# MCU_Design_exp_neat.net
KiCad netlist of a schematic drawn in EAGLE
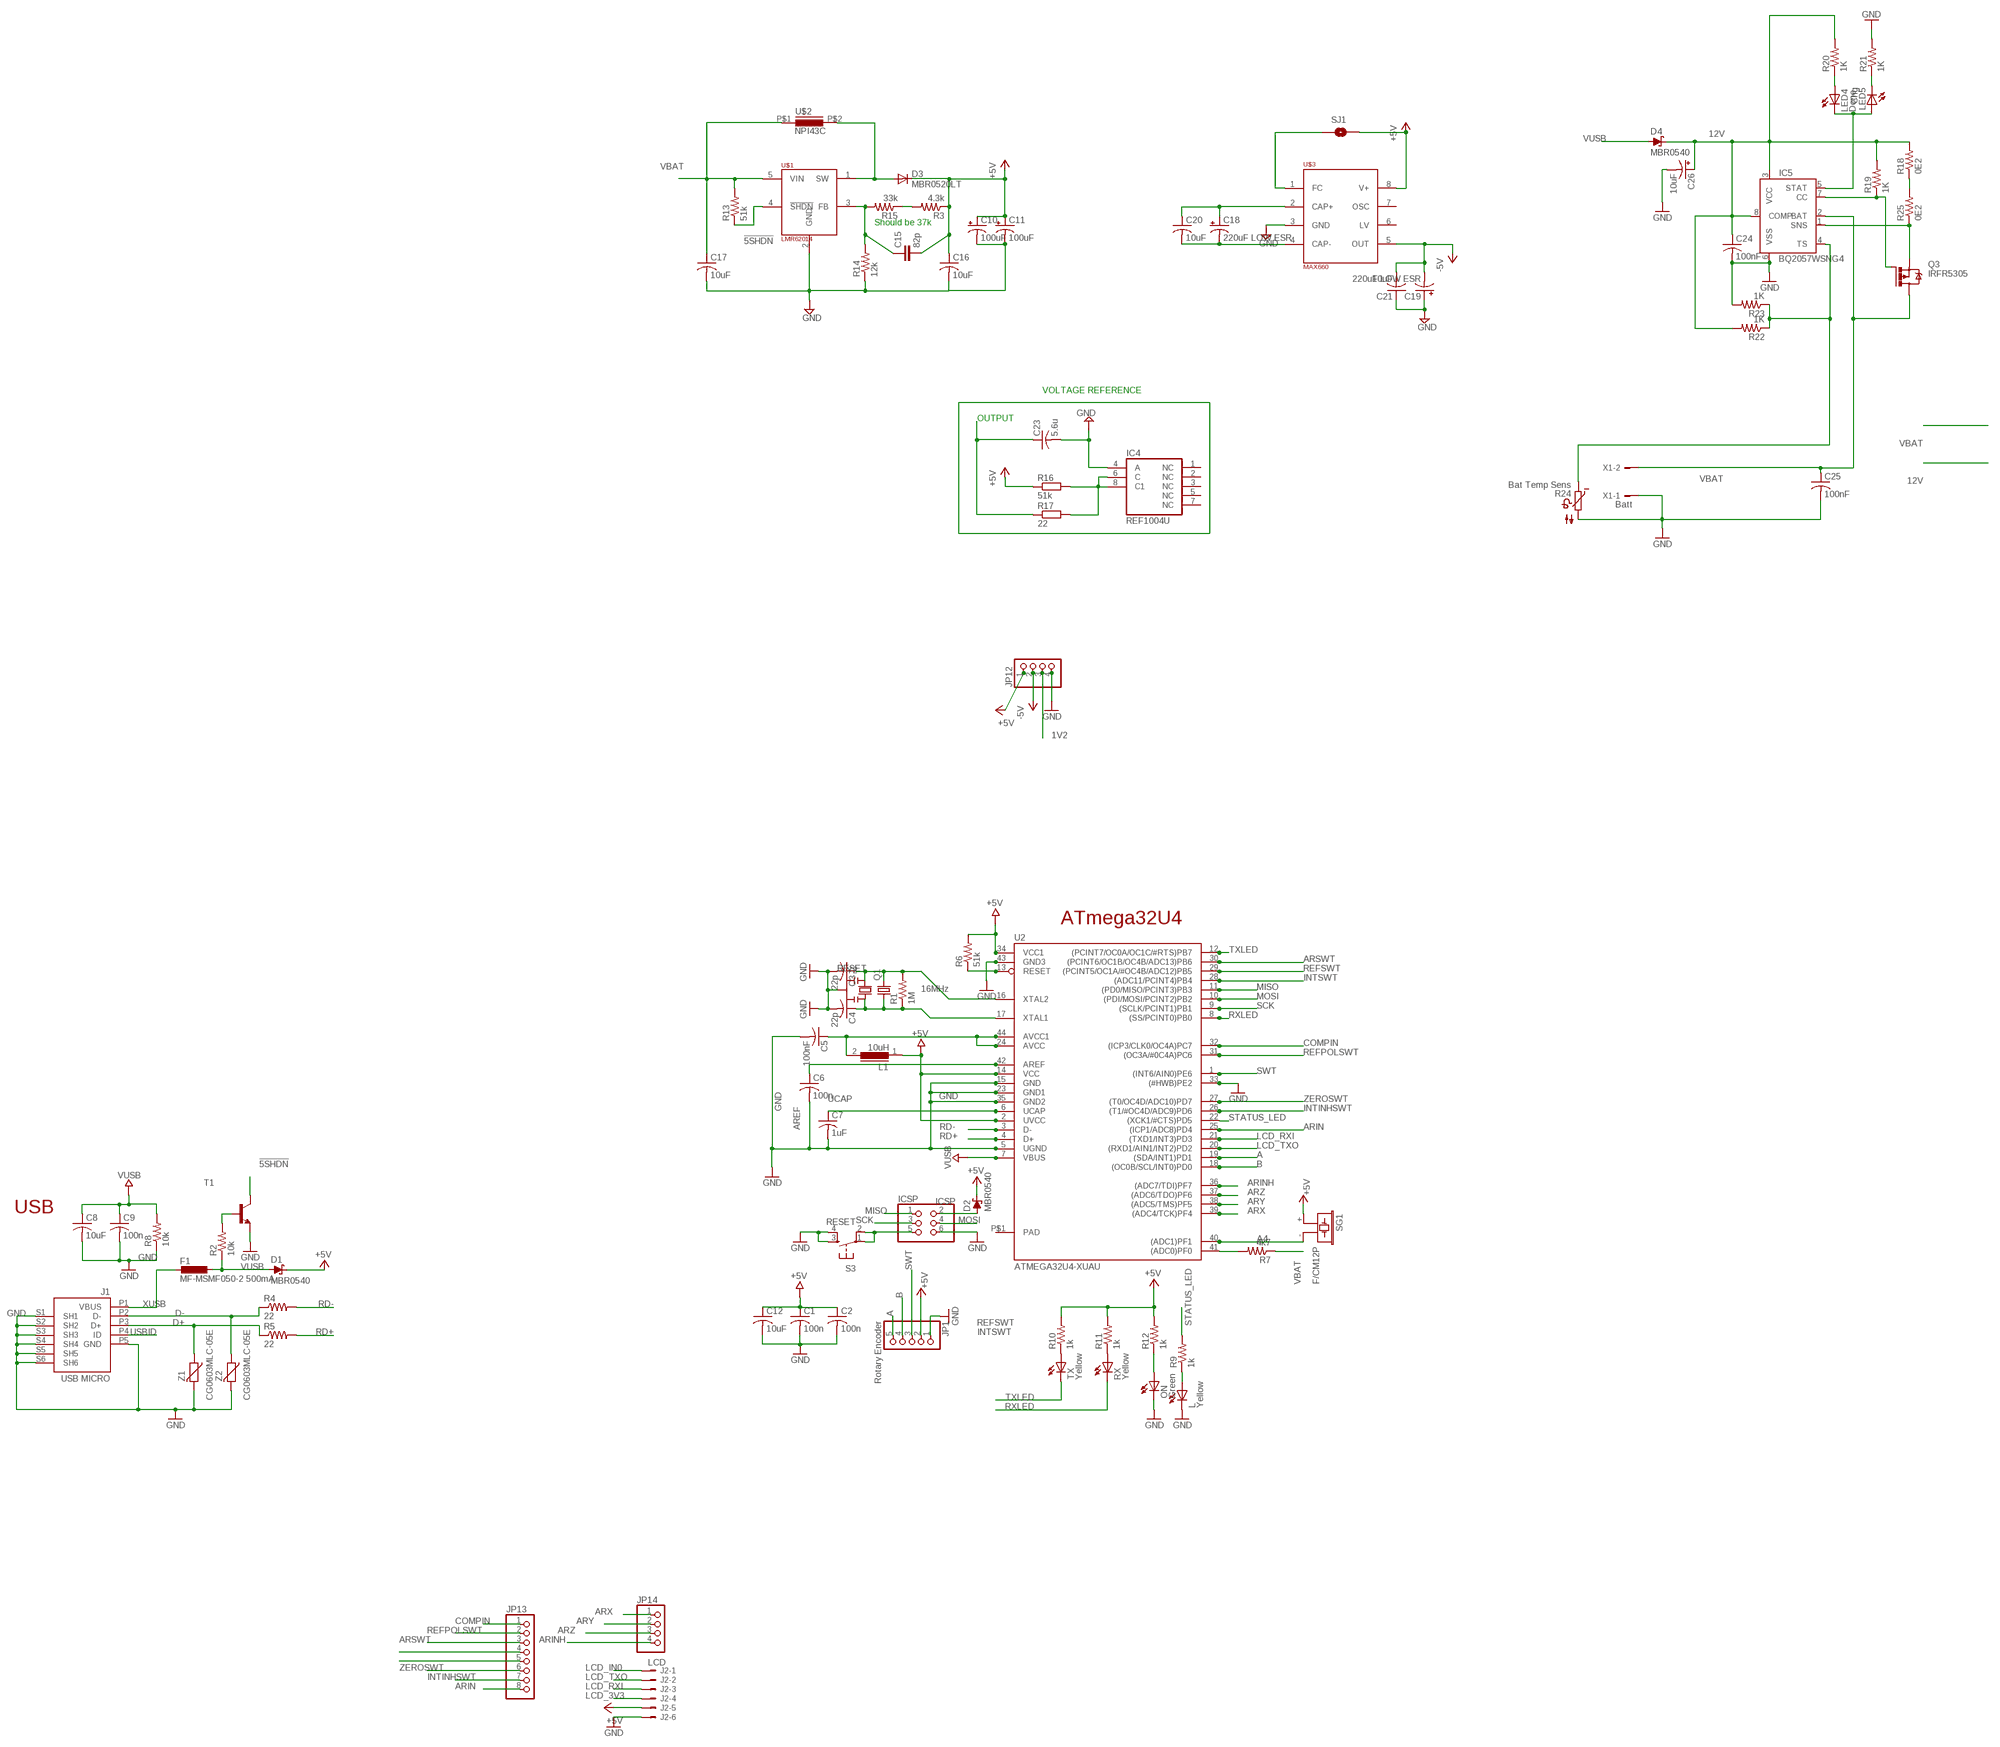
[diagram p0: schematic, sheet 1]

(export (version "E")
  (design (tool "Eeschema 10.0.6"))
  (components
    (comp (ref "C1")
      (value "100n")
      (footprint "eagle-import:C0805")
      (libsource (lib "eagle-import") (part "resistor_C-USC0805"))
    )
    (comp (ref "C2")
      (value "100n")
      (footprint "eagle-import:C0805")
      (libsource (lib "eagle-import") (part "resistor_C-USC0805"))
    )
    (comp (ref "C3")
      (value "22p")
      (footprint "eagle-import:C0805")
      (libsource (lib "eagle-import") (part "resistor_C-USC0805"))
    )
    (comp (ref "C4")
      (value "22p")
      (footprint "eagle-import:C0805")
      (libsource (lib "eagle-import") (part "resistor_C-USC0805"))
    )
    (comp (ref "C5")
      (value "100nF")
      (footprint "eagle-import:C0805")
      (libsource (lib "eagle-import") (part "resistor_C-USC0805"))
    )
    (comp (ref "C6")
      (value "100n")
      (footprint "eagle-import:C0805")
      (libsource (lib "eagle-import") (part "resistor_C-USC0805"))
    )
    (comp (ref "C7")
      (value "1uF")
      (footprint "eagle-import:C0805")
      (libsource (lib "eagle-import") (part "resistor_C-USC0805"))
    )
    (comp (ref "C8")
      (value "10uF")
      (footprint "eagle-import:C0805")
      (libsource (lib "eagle-import") (part "resistor_C-USC0805"))
    )
    (comp (ref "C9")
      (value "100n")
      (footprint "eagle-import:C0805")
      (libsource (lib "eagle-import") (part "resistor_C-USC0805"))
    )
    (comp (ref "C10")
      (value "100uF")
      (footprint "eagle-import:PANASONIC_D")
      (libsource (lib "eagle-import") (part "CPOL-USD"))
    )
    (comp (ref "C11")
      (value "100uF")
      (footprint "eagle-import:PANASONIC_D")
      (libsource (lib "eagle-import") (part "CPOL-USD"))
    )
    (comp (ref "C12")
      (value "10uF")
      (footprint "eagle-import:C0805")
      (libsource (lib "eagle-import") (part "resistor_C-USC0805"))
    )
    (comp (ref "C15")
      (value "82p")
      (footprint "eagle-import:C0805")
      (libsource (lib "eagle-import") (part "C-EUC0805"))
    )
    (comp (ref "C16")
      (value "10uF")
      (footprint "eagle-import:C0805")
      (libsource (lib "eagle-import") (part "resistor_C-USC0805"))
    )
    (comp (ref "C17")
      (value "10uF")
      (footprint "eagle-import:C0805")
      (libsource (lib "eagle-import") (part "resistor_C-USC0805"))
    )
    (comp (ref "C18")
      (value "220uF LOW ESR")
      (footprint "eagle-import:PANASONIC_D")
      (libsource (lib "eagle-import") (part "CPOL-USD"))
    )
    (comp (ref "C19")
      (value "220uF LOW ESR")
      (footprint "eagle-import:PANASONIC_D")
      (libsource (lib "eagle-import") (part "CPOL-USD"))
    )
    (comp (ref "C20")
      (value "10uF")
      (footprint "eagle-import:C0805")
      (libsource (lib "eagle-import") (part "resistor_C-USC0805"))
    )
    (comp (ref "C21")
      (value "10uF")
      (footprint "eagle-import:C0805")
      (libsource (lib "eagle-import") (part "resistor_C-USC0805"))
    )
    (comp (ref "C23")
      (value "5.6u")
      (footprint "eagle-import:C0805K")
      (libsource (lib "eagle-import") (part "C-USC0805K"))
    )
    (comp (ref "C24")
      (value "100nF")
      (footprint "eagle-import:C0805K")
      (libsource (lib "eagle-import") (part "resistor_C-USC0805K"))
    )
    (comp (ref "C25")
      (value "100nF")
      (footprint "eagle-import:C0805K")
      (libsource (lib "eagle-import") (part "resistor_C-USC0805K"))
    )
    (comp (ref "C26")
      (value "10uF")
      (footprint "eagle-import:153CLV-0405")
      (libsource (lib "eagle-import") (part "CPOL-US153CLV-0405"))
    )
    (comp (ref "D1")
      (value "MBR0540")
      (footprint "eagle-import:SOD123@2")
      (libsource (lib "eagle-import") (part "MBR0540"))
    )
    (comp (ref "D2")
      (value "MBR0540")
      (footprint "eagle-import:SOD123@2")
      (libsource (lib "eagle-import") (part "MBR0540"))
    )
    (comp (ref "D3")
      (value "MBR0520LT")
      (footprint "eagle-import:SOD123")
      (libsource (lib "eagle-import") (part "MBR0520LT"))
    )
    (comp (ref "D4")
      (value "MBR0540")
      (footprint "eagle-import:SOD123@2")
      (libsource (lib "eagle-import") (part "MBR0540"))
    )
    (comp (ref "F1")
      (value "MF-MSMF050-2 500mA")
      (footprint "eagle-import:L1812")
      (libsource (lib "eagle-import") (part "L-EUL1812"))
    )
    (comp (ref "IC4")
      (value "REF1004U")
      (footprint "eagle-import:SO08")
      (fields (field (name "MF") "TEXAS INSTRUMENTS") (field (name "MPN") "REF1004C-1.2"))
      (libsource (lib "eagle-import") (part "REF1004U"))
    )
    (comp (ref "IC5")
      (value "BQ2057WSNG4")
      (footprint "eagle-import:D_R-PDSO-G8")
      (libsource (lib "eagle-import") (part "BQ2057WSNG4"))
    )
    (comp (ref "ICSP")
      (value "ICSP")
      (footprint "eagle-import:2X03")
      (libsource (lib "eagle-import") (part "PINHD-2X3"))
    )
    (comp (ref "J1")
      (value "USB MICRO")
      (footprint "eagle-import:CON2_USB_MICRO_B_AT")
      (libsource (lib "eagle-import") (part "MYCON2_USB-MINI-B"))
    )
    (comp (ref "J2")
      (value "LCD")
      (footprint "eagle-import:7395-06")
      (libsource (lib "eagle-import") (part "22-?-0605-7068"))
    )
    (comp (ref "JP1")
      (value "Rotary Encoder")
      (footprint "eagle-import:1X05")
      (libsource (lib "eagle-import") (part "PINHD-1X5"))
    )
    (comp (ref "JP12")
      (value "PINHD-1X4")
      (footprint "eagle-import:1X04")
      (libsource (lib "eagle-import") (part "PINHD-1X4"))
    )
    (comp (ref "JP13")
      (value "PINHD-1X8")
      (footprint "eagle-import:1X08")
      (libsource (lib "eagle-import") (part "PINHD-1X8"))
    )
    (comp (ref "JP14")
      (value "PINHD-1X4")
      (footprint "eagle-import:1X04")
      (libsource (lib "eagle-import") (part "PINHD-1X4"))
    )
    (comp (ref "L")
      (value "Yellow")
      (footprint "eagle-import:CHIPLED_0805")
      (libsource (lib "eagle-import") (part "LEDCHIPLED_0805"))
    )
    (comp (ref "L1")
      (value "10uH")
      (footprint "eagle-import:MMICC7")
      (libsource (lib "eagle-import") (part "MMICC7"))
    )
    (comp (ref "LED4")
      (value "Done")
      (footprint "eagle-import:CHIPLED_0805")
      (libsource (lib "eagle-import") (part "LEDCHIPLED_0805"))
    )
    (comp (ref "LED5")
      (value "Chg")
      (footprint "eagle-import:CHIPLED_0805")
      (libsource (lib "eagle-import") (part "LEDCHIPLED_0805"))
    )
    (comp (ref "ON")
      (value "Green")
      (footprint "eagle-import:CHIPLED_0805")
      (libsource (lib "eagle-import") (part "LEDCHIPLED_0805"))
    )
    (comp (ref "Q1")
      (value "CRYSTALHC49UP")
      (footprint "eagle-import:HC49UP")
      (libsource (lib "eagle-import") (part "CRYSTALHC49UP"))
    )
    (comp (ref "Q3")
      (value "IRFR5305")
      (footprint "eagle-import:D-PAK_TO252AA")
      (libsource (lib "eagle-import") (part "IRF?5305R"))
    )
    (comp (ref "R1")
      (value "1M")
      (footprint "eagle-import:R0805")
      (libsource (lib "eagle-import") (part "R-US_R0805"))
    )
    (comp (ref "R2")
      (value "10k")
      (footprint "eagle-import:R0805")
      (libsource (lib "eagle-import") (part "R-US_R0805"))
    )
    (comp (ref "R3")
      (value "4.3k")
      (footprint "eagle-import:R0805")
      (libsource (lib "eagle-import") (part "R-US_R0805"))
    )
    (comp (ref "R4")
      (value "22")
      (footprint "eagle-import:R0805")
      (libsource (lib "eagle-import") (part "R-US_R0805"))
    )
    (comp (ref "R5")
      (value "22")
      (footprint "eagle-import:R0805")
      (libsource (lib "eagle-import") (part "R-US_R0805"))
    )
    (comp (ref "R6")
      (value "51k")
      (footprint "eagle-import:R0805")
      (libsource (lib "eagle-import") (part "R-US_R0805"))
    )
    (comp (ref "R7")
      (value "4k7")
      (footprint "eagle-import:R0805")
      (libsource (lib "eagle-import") (part "R-US_R0805"))
    )
    (comp (ref "R8")
      (value "10k")
      (footprint "eagle-import:R0805")
      (libsource (lib "eagle-import") (part "R-US_R0805"))
    )
    (comp (ref "R9")
      (value "1k")
      (footprint "eagle-import:R0805")
      (libsource (lib "eagle-import") (part "R-US_R0805"))
    )
    (comp (ref "R10")
      (value "1k")
      (footprint "eagle-import:R0805")
      (libsource (lib "eagle-import") (part "R-US_R0805"))
    )
    (comp (ref "R11")
      (value "1k")
      (footprint "eagle-import:R0805")
      (libsource (lib "eagle-import") (part "R-US_R0805"))
    )
    (comp (ref "R12")
      (value "1k")
      (footprint "eagle-import:R0805")
      (libsource (lib "eagle-import") (part "R-US_R0805"))
    )
    (comp (ref "R13")
      (value "51k")
      (footprint "eagle-import:R0805")
      (libsource (lib "eagle-import") (part "R-US_R0805"))
    )
    (comp (ref "R14")
      (value "12k")
      (footprint "eagle-import:R0805")
      (libsource (lib "eagle-import") (part "R-US_R0805"))
    )
    (comp (ref "R15")
      (value "33k")
      (footprint "eagle-import:R0805")
      (libsource (lib "eagle-import") (part "R-US_R0805"))
    )
    (comp (ref "R16")
      (value "51k")
      (footprint "eagle-import:M0805")
      (libsource (lib "eagle-import") (part "R-EU_M0805"))
    )
    (comp (ref "R17")
      (value "22")
      (footprint "eagle-import:M0805")
      (libsource (lib "eagle-import") (part "R-EU_M0805"))
    )
    (comp (ref "R18")
      (value "0E2")
      (footprint "eagle-import:M1206")
      (libsource (lib "eagle-import") (part "R-US_M1206"))
    )
    (comp (ref "R19")
      (value "1K")
      (footprint "eagle-import:R0805")
      (libsource (lib "eagle-import") (part "R-US_R0805"))
    )
    (comp (ref "R20")
      (value "1K")
      (footprint "eagle-import:R0805")
      (libsource (lib "eagle-import") (part "R-US_R0805"))
    )
    (comp (ref "R21")
      (value "1K")
      (footprint "eagle-import:R0805")
      (libsource (lib "eagle-import") (part "R-US_R0805"))
    )
    (comp (ref "R22")
      (value "1K")
      (footprint "eagle-import:R0805")
      (libsource (lib "eagle-import") (part "R-US_R0805"))
    )
    (comp (ref "R23")
      (value "1K")
      (footprint "eagle-import:R0805")
      (libsource (lib "eagle-import") (part "R-US_R0805"))
    )
    (comp (ref "R24")
      (value "Bat Temp Sens")
      (footprint "eagle-import:P640")
      (libsource (lib "eagle-import") (part "NTC640"))
    )
    (comp (ref "R25")
      (value "0E2")
      (footprint "eagle-import:M1206")
      (libsource (lib "eagle-import") (part "R-US_M1206"))
    )
    (comp (ref "RX")
      (value "Yellow")
      (footprint "eagle-import:CHIPLED_0805")
      (libsource (lib "eagle-import") (part "LEDCHIPLED_0805"))
    )
    (comp (ref "S3")
      (value "RESET")
      (footprint "eagle-import:TACTILE_SWITCH_SMD")
      (libsource (lib "eagle-import") (part "TAC_SWITCHSMD"))
    )
    (comp (ref "SG1")
      (value "F/CM12P")
      (footprint "eagle-import:F_CM12P")
      (libsource (lib "eagle-import") (part "F/CM12P"))
    )
    (comp (ref "SJ1")
      (value "SOLDERJUMPERTRACE")
      (footprint "eagle-import:SJ_2S-TRACE")
      (libsource (lib "eagle-import") (part "SOLDERJUMPERTRACE"))
    )
    (comp (ref "T1")
      (value "MMBT2222ALT1-NPN-SOT23-BEC")
      (footprint "eagle-import:SOT23-BEC")
      (libsource (lib "eagle-import") (part "-NPN-SOT23-BECMMBT2222ALT1"))
    )
    (comp (ref "TX")
      (value "Yellow")
      (footprint "eagle-import:CHIPLED_0805")
      (libsource (lib "eagle-import") (part "LEDCHIPLED_0805"))
    )
    (comp (ref "U$1")
      (value "LMR62014")
      (footprint "eagle-import:SOT23-5")
      (libsource (lib "eagle-import") (part "LMR62014"))
    )
    (comp (ref "U$2")
      (value "NPI43C")
      (footprint "eagle-import:NPI43C")
      (libsource (lib "eagle-import") (part "NPI43C"))
    )
    (comp (ref "U$3")
      (value "MAX660")
      (footprint "eagle-import:SO08")
      (libsource (lib "eagle-import") (part "MAX660"))
    )
    (comp (ref "U2")
      (value "ATMEGA32U4-XUAU")
      (footprint "eagle-import:TQFP44-PAD")
      (libsource (lib "eagle-import") (part "ATMEGA32U4-XUAU"))
    )
    (comp (ref "X1")
      (value "Batt")
      (footprint "eagle-import:22-23-2021")
      (fields (field (name "MF") "MOLEX") (field (name "MPN") "22-23-2021"))
      (libsource (lib "eagle-import") (part "22-23-2021"))
    )
    (comp (ref "Y2")
      (value "16MHz")
      (footprint "eagle-import:RESONATOR")
      (libsource (lib "eagle-import") (part "RESONATORMU"))
    )
    (comp (ref "Z1")
      (value "CG0603MLC-05E")
      (footprint "eagle-import:CT_CN0603")
      (libsource (lib "eagle-import") (part "VARISTORCN0603"))
    )
    (comp (ref "Z2")
      (value "CG0603MLC-05E")
      (footprint "eagle-import:CT_CN0603")
      (libsource (lib "eagle-import") (part "VARISTORCN0603"))
    )
  )
  (nets
    (net (code "1") (name "+5V") (class "Default")
      (node (ref "C1") (pin "1") (pinfunction "1_1") (pintype "passive"))
      (node (ref "C10") (pin "+") (pinfunction "+_+") (pintype "passive"))
      (node (ref "C11") (pin "+") (pinfunction "+_+") (pintype "passive"))
      (node (ref "C12") (pin "1") (pinfunction "1_1") (pintype "passive"))
      (node (ref "C15") (pin "2") (pinfunction "2_2") (pintype "passive"))
      (node (ref "C16") (pin "1") (pinfunction "1_1") (pintype "passive"))
      (node (ref "C2") (pin "1") (pinfunction "1_1") (pintype "passive"))
      (node (ref "D1") (pin "C") (pinfunction "C_C") (pintype "passive"))
      (node (ref "D2") (pin "C") (pinfunction "C_C") (pintype "passive"))
      (node (ref "D3") (pin "C") (pinfunction "C_C") (pintype "passive"))
      (node (ref "J2") (pin "5") (pinfunction "S_5") (pintype "passive"))
      (node (ref "JP1") (pin "2") (pinfunction "2_2") (pintype "passive"))
      (node (ref "JP12") (pin "1") (pinfunction "1_1") (pintype "passive"))
      (node (ref "L1") (pin "1") (pinfunction "1_1") (pintype "passive"))
      (node (ref "R10") (pin "2") (pinfunction "2_2") (pintype "passive"))
      (node (ref "R11") (pin "2") (pinfunction "2_2") (pintype "passive"))
      (node (ref "R12") (pin "2") (pinfunction "2_2") (pintype "passive"))
      (node (ref "R16") (pin "1") (pinfunction "1_1") (pintype "passive"))
      (node (ref "R3") (pin "1") (pinfunction "1_1") (pintype "passive"))
      (node (ref "R6") (pin "2") (pinfunction "2_2") (pintype "passive"))
      (node (ref "SG1") (pin "+") (pinfunction "1_+") (pintype "passive"))
      (node (ref "SJ1") (pin "2") (pinfunction "2_2") (pintype "passive"))
      (node (ref "U$3") (pin "8") (pinfunction "V+_8") (pintype "bidirectional"))
      (node (ref "U2") (pin "14") (pinfunction "VCC_14") (pintype "power_in"))
      (node (ref "U2") (pin "2") (pinfunction "UVCC_2") (pintype "power_in"))
      (node (ref "U2") (pin "34") (pinfunction "VCC1_34") (pintype "power_in"))
    )
    (net (code "2") (name "-5V") (class "Default")
      (node (ref "C19") (pin "-") (pinfunction "-_-") (pintype "passive"))
      (node (ref "C21") (pin "2") (pinfunction "2_2") (pintype "passive"))
      (node (ref "JP12") (pin "2") (pinfunction "2_2") (pintype "passive"))
      (node (ref "U$3") (pin "5") (pinfunction "OUT_5") (pintype "bidirectional"))
    )
    (net (code "3") (name "/1V2") (class "Default")
      (node (ref "C23") (pin "1") (pinfunction "1_1") (pintype "passive"))
      (node (ref "JP12") (pin "3") (pinfunction "3_3") (pintype "passive"))
      (node (ref "R17") (pin "1") (pinfunction "1_1") (pintype "passive"))
    )
    (net (code "4") (name "/12V") (class "Default")
      (node (ref "C24") (pin "1") (pinfunction "1_1") (pintype "passive"))
      (node (ref "C26") (pin "+") (pinfunction "+_+") (pintype "passive"))
      (node (ref "D4") (pin "C") (pinfunction "C_C") (pintype "passive"))
      (node (ref "IC5") (pin "3") (pinfunction "VCC_3") (pintype "input"))
      (node (ref "IC5") (pin "8") (pinfunction "COMP_8") (pintype "input"))
      (node (ref "R18") (pin "2") (pinfunction "2_2") (pintype "passive"))
      (node (ref "R19") (pin "2") (pinfunction "2_2") (pintype "passive"))
      (node (ref "R20") (pin "2") (pinfunction "2_2") (pintype "passive"))
      (node (ref "R22") (pin "2") (pinfunction "2_2") (pintype "passive"))
    )
    (net (code "5") (name "/A") (class "Default")
      (node (ref "JP1") (pin "5") (pinfunction "5_5") (pintype "passive"))
      (node (ref "U2") (pin "19") (pinfunction "(SDA/INT1)PD1_19") (pintype "bidirectional"))
    )
    (net (code "6") (name "/A4") (class "Default")
      (node (ref "SG1") (pin "-") (pinfunction "2_-") (pintype "passive"))
      (node (ref "U2") (pin "40") (pinfunction "(ADC1)PF1_40") (pintype "bidirectional"))
    )
    (net (code "7") (name "/AREF") (class "Default")
      (node (ref "C6") (pin "1") (pinfunction "1_1") (pintype "passive"))
      (node (ref "U2") (pin "42") (pinfunction "AREF_42") (pintype "power_in"))
    )
    (net (code "8") (name "/ARIN") (class "Default")
      (node (ref "JP13") (pin "8") (pinfunction "8_8") (pintype "passive"))
      (node (ref "U2") (pin "25") (pinfunction "(ICP1/ADC8)PD4_25") (pintype "bidirectional"))
    )
    (net (code "9") (name "/ARINH") (class "Default")
      (node (ref "JP14") (pin "4") (pinfunction "4_4") (pintype "passive"))
      (node (ref "U2") (pin "36") (pinfunction "(ADC7/TDI)PF7_36") (pintype "bidirectional"))
    )
    (net (code "10") (name "/ARSWT") (class "Default")
      (node (ref "JP13") (pin "3") (pinfunction "3_3") (pintype "passive"))
      (node (ref "U2") (pin "30") (pinfunction "(PCINT6/OC1B/OC4B/ADC13)PB6_30") (pintype "bidirectional"))
    )
    (net (code "11") (name "/ARX") (class "Default")
      (node (ref "JP14") (pin "1") (pinfunction "1_1") (pintype "passive"))
      (node (ref "U2") (pin "39") (pinfunction "(ADC4/TCK)PF4_39") (pintype "bidirectional"))
    )
    (net (code "12") (name "/ARY") (class "Default")
      (node (ref "JP14") (pin "2") (pinfunction "2_2") (pintype "passive"))
      (node (ref "U2") (pin "38") (pinfunction "(ADC5/TMS)PF5_38") (pintype "bidirectional"))
    )
    (net (code "13") (name "/ARZ") (class "Default")
      (node (ref "JP14") (pin "3") (pinfunction "3_3") (pintype "passive"))
      (node (ref "U2") (pin "37") (pinfunction "(ADC6/TDO)PF6_37") (pintype "bidirectional"))
    )
    (net (code "14") (name "/B") (class "Default")
      (node (ref "JP1") (pin "4") (pinfunction "4_4") (pintype "passive"))
      (node (ref "U2") (pin "18") (pinfunction "(OC0B/SCL/INT0)PD0_18") (pintype "bidirectional"))
    )
    (net (code "15") (name "/COMPIN") (class "Default")
      (node (ref "JP13") (pin "1") (pinfunction "1_1") (pintype "passive"))
      (node (ref "U2") (pin "32") (pinfunction "(ICP3/CLK0/OC4A)PC7_32") (pintype "bidirectional"))
    )
    (net (code "16") (name "/D+") (class "Default")
      (node (ref "J1") (pin "P3") (pinfunction "D+_P3") (pintype "bidirectional"))
      (node (ref "R5") (pin "1") (pinfunction "1_1") (pintype "passive"))
      (node (ref "Z1") (pin "1") (pinfunction "1_1") (pintype "passive"))
    )
    (net (code "17") (name "/D-") (class "Default")
      (node (ref "J1") (pin "P2") (pinfunction "D-_P2") (pintype "bidirectional"))
      (node (ref "R4") (pin "1") (pinfunction "1_1") (pintype "passive"))
      (node (ref "Z2") (pin "1") (pinfunction "1_1") (pintype "passive"))
    )
    (net (code "18") (name "/INTINHSWT") (class "Default")
      (node (ref "JP13") (pin "7") (pinfunction "7_7") (pintype "passive"))
      (node (ref "U2") (pin "26") (pinfunction "(T1/#OC4D/ADC9)PD6_26") (pintype "bidirectional"))
    )
    (net (code "19") (name "/INTSWT") (class "Default")
      (node (ref "JP13") (pin "5") (pinfunction "5_5") (pintype "passive"))
      (node (ref "U2") (pin "28") (pinfunction "(ADC11/PCINT4)PB4_28") (pintype "bidirectional"))
    )
    (net (code "20") (name "/LCD_3V3") (class "Default")
      (node (ref "J2") (pin "4") (pinfunction "S_4") (pintype "passive"))
    )
    (net (code "21") (name "/LCD_IN0") (class "Default")
      (node (ref "J2") (pin "1") (pinfunction "S_1") (pintype "passive"))
    )
    (net (code "22") (name "/LCD_RXI") (class "Default")
      (node (ref "J2") (pin "3") (pinfunction "S_3") (pintype "passive"))
      (node (ref "U2") (pin "21") (pinfunction "(TXD1/INT3)PD3_21") (pintype "bidirectional"))
    )
    (net (code "23") (name "/LCD_TXO") (class "Default")
      (node (ref "J2") (pin "2") (pinfunction "S_2") (pintype "passive"))
      (node (ref "U2") (pin "20") (pinfunction "(RXD1/AIN1/INT2)PD2_20") (pintype "bidirectional"))
    )
    (net (code "24") (name "/MISO") (class "Default")
      (node (ref "ICSP") (pin "1") (pinfunction "1_1") (pintype "passive"))
      (node (ref "U2") (pin "11") (pinfunction "(PD0/MISO/PCINT3)PB3_11") (pintype "bidirectional"))
    )
    (net (code "25") (name "/MOSI") (class "Default")
      (node (ref "ICSP") (pin "4") (pinfunction "4_4") (pintype "passive"))
      (node (ref "U2") (pin "10") (pinfunction "(PDI/MOSI/PCINT2)PB2_10") (pintype "bidirectional"))
    )
    (net (code "26") (name "/PAD") (class "Default")
      (node (ref "U2") (pin "P$1") (pinfunction "PAD_P$1") (pintype "power_in"))
    )
    (net (code "27") (name "/RD+") (class "Default")
      (node (ref "R5") (pin "2") (pinfunction "2_2") (pintype "passive"))
      (node (ref "U2") (pin "4") (pinfunction "D+_4") (pintype "bidirectional"))
    )
    (net (code "28") (name "/RD-") (class "Default")
      (node (ref "R4") (pin "2") (pinfunction "2_2") (pintype "passive"))
      (node (ref "U2") (pin "3") (pinfunction "D-_3") (pintype "bidirectional"))
    )
    (net (code "29") (name "/REFPOLSWT") (class "Default")
      (node (ref "JP13") (pin "2") (pinfunction "2_2") (pintype "passive"))
      (node (ref "U2") (pin "31") (pinfunction "(OC3A/#0C4A)PC6_31") (pintype "bidirectional"))
    )
    (net (code "30") (name "/REFSWT") (class "Default")
      (node (ref "JP13") (pin "4") (pinfunction "4_4") (pintype "passive"))
      (node (ref "U2") (pin "29") (pinfunction "(PCINT5/OC1A/#OC4B/ADC12)PB5_29") (pintype "bidirectional"))
    )
    (net (code "31") (name "/RESET") (class "Default")
      (node (ref "R6") (pin "1") (pinfunction "1_1") (pintype "passive"))
      (node (ref "U2") (pin "13") (pinfunction "RESET_13") (pintype "input"))
    )
    (net (code "32") (name "/RXLED") (class "Default")
      (node (ref "RX") (pin "C") (pinfunction "C_C") (pintype "passive"))
      (node (ref "U2") (pin "8") (pinfunction "(SS/PCINT0)PB0_8") (pintype "bidirectional"))
    )
    (net (code "33") (name "/SCK") (class "Default")
      (node (ref "ICSP") (pin "3") (pinfunction "3_3") (pintype "passive"))
      (node (ref "U2") (pin "9") (pinfunction "(SCLK/PCINT1)PB1_9") (pintype "bidirectional"))
    )
    (net (code "34") (name "/STATUS_LED") (class "Default")
      (node (ref "R9") (pin "2") (pinfunction "2_2") (pintype "passive"))
      (node (ref "U2") (pin "22") (pinfunction "(XCK1/#CTS)PD5_22") (pintype "bidirectional"))
    )
    (net (code "35") (name "/SWT") (class "Default")
      (node (ref "JP1") (pin "3") (pinfunction "3_3") (pintype "passive"))
      (node (ref "U2") (pin "1") (pinfunction "(INT6/AIN0)PE6_1") (pintype "bidirectional"))
    )
    (net (code "36") (name "/TXLED") (class "Default")
      (node (ref "TX") (pin "C") (pinfunction "C_C") (pintype "passive"))
      (node (ref "U2") (pin "12") (pinfunction "(PCINT7/OC0A/OC1C/#RTS)PB7_12") (pintype "bidirectional"))
    )
    (net (code "37") (name "/UCAP") (class "Default")
      (node (ref "C7") (pin "1") (pinfunction "1_1") (pintype "passive"))
      (node (ref "U2") (pin "6") (pinfunction "UCAP_6") (pintype "passive"))
    )
    (net (code "38") (name "/USBID") (class "Default")
      (node (ref "J1") (pin "P4") (pinfunction "ID_P4") (pintype "bidirectional"))
    )
    (net (code "39") (name "/VBAT") (class "Default")
      (node (ref "C17") (pin "1") (pinfunction "1_1") (pintype "passive"))
      (node (ref "C25") (pin "1") (pinfunction "1_1") (pintype "passive"))
      (node (ref "IC5") (pin "2") (pinfunction "BAT_2") (pintype "input"))
      (node (ref "Q3") (pin "4") (pinfunction "D_4") (pintype "passive"))
      (node (ref "R13") (pin "2") (pinfunction "2_2") (pintype "passive"))
      (node (ref "R7") (pin "1") (pinfunction "1_1") (pintype "passive"))
      (node (ref "U$1") (pin "5") (pinfunction "VIN_5") (pintype "bidirectional"))
      (node (ref "U$2") (pin "P$1") (pinfunction "1_P$1") (pintype "passive"))
      (node (ref "X1") (pin "2") (pinfunction "S_2") (pintype "passive"))
    )
    (net (code "40") (name "/XUSB") (class "Default")
      (node (ref "F1") (pin "2") (pinfunction "2_2") (pintype "passive"))
      (node (ref "J1") (pin "P1") (pinfunction "VBUS_P1") (pintype "power_in"))
    )
    (net (code "41") (name "/ZEROSWT") (class "Default")
      (node (ref "JP13") (pin "6") (pinfunction "6_6") (pintype "passive"))
      (node (ref "U2") (pin "27") (pinfunction "(T0/OC4D/ADC10)PD7_27") (pintype "bidirectional"))
    )
    (net (code "42") (name "/~{5SHDN}") (class "Default")
      (node (ref "R13") (pin "1") (pinfunction "1_1") (pintype "passive"))
      (node (ref "T1") (pin "C") (pinfunction "C_C") (pintype "passive"))
      (node (ref "U$1") (pin "4") (pinfunction "~{SHDN}_4") (pintype "bidirectional"))
    )
    (net (code "43") (name "GND") (class "Default")
      (node (ref "C1") (pin "2") (pinfunction "2_2") (pintype "passive"))
      (node (ref "C10") (pin "-") (pinfunction "-_-") (pintype "passive"))
      (node (ref "C11") (pin "-") (pinfunction "-_-") (pintype "passive"))
      (node (ref "C12") (pin "2") (pinfunction "2_2") (pintype "passive"))
      (node (ref "C16") (pin "2") (pinfunction "2_2") (pintype "passive"))
      (node (ref "C17") (pin "2") (pinfunction "2_2") (pintype "passive"))
      (node (ref "C19") (pin "+") (pinfunction "+_+") (pintype "passive"))
      (node (ref "C2") (pin "2") (pinfunction "2_2") (pintype "passive"))
      (node (ref "C21") (pin "1") (pinfunction "1_1") (pintype "passive"))
      (node (ref "C23") (pin "2") (pinfunction "2_2") (pintype "passive"))
      (node (ref "C24") (pin "2") (pinfunction "2_2") (pintype "passive"))
      (node (ref "C25") (pin "2") (pinfunction "2_2") (pintype "passive"))
      (node (ref "C26") (pin "-") (pinfunction "-_-") (pintype "passive"))
      (node (ref "C3") (pin "2") (pinfunction "2_2") (pintype "passive"))
      (node (ref "C4") (pin "2") (pinfunction "2_2") (pintype "passive"))
      (node (ref "C5") (pin "2") (pinfunction "2_2") (pintype "passive"))
      (node (ref "C6") (pin "2") (pinfunction "2_2") (pintype "passive"))
      (node (ref "C7") (pin "2") (pinfunction "2_2") (pintype "passive"))
      (node (ref "C8") (pin "2") (pinfunction "2_2") (pintype "passive"))
      (node (ref "C9") (pin "2") (pinfunction "2_2") (pintype "passive"))
      (node (ref "IC4") (pin "4") (pinfunction "A_4") (pintype "passive"))
      (node (ref "IC5") (pin "6") (pinfunction "VSS_6") (pintype "power_in"))
      (node (ref "ICSP") (pin "6") (pinfunction "6_6") (pintype "passive"))
      (node (ref "J1") (pin "P5") (pinfunction "GND_P5") (pintype "passive"))
      (node (ref "J1") (pin "S1") (pinfunction "SH1_S1") (pintype "passive"))
      (node (ref "J1") (pin "S2") (pinfunction "SH2_S2") (pintype "passive"))
      (node (ref "J1") (pin "S3") (pinfunction "SH3_S3") (pintype "passive"))
      (node (ref "J1") (pin "S4") (pinfunction "SH4_S4") (pintype "passive"))
      (node (ref "J1") (pin "S5") (pinfunction "SH5_S5") (pintype "passive"))
      (node (ref "J1") (pin "S6") (pinfunction "SH6_S6") (pintype "passive"))
      (node (ref "J2") (pin "6") (pinfunction "S_6") (pintype "passive"))
      (node (ref "JP1") (pin "1") (pinfunction "1_1") (pintype "passive"))
      (node (ref "JP12") (pin "4") (pinfunction "4_4") (pintype "passive"))
      (node (ref "L") (pin "C") (pinfunction "C_C") (pintype "passive"))
      (node (ref "ON") (pin "C") (pinfunction "C_C") (pintype "passive"))
      (node (ref "R14") (pin "1") (pinfunction "1_1") (pintype "passive"))
      (node (ref "R21") (pin "2") (pinfunction "2_2") (pintype "passive"))
      (node (ref "R23") (pin "2") (pinfunction "2_2") (pintype "passive"))
      (node (ref "R24") (pin "2") (pinfunction "2_2") (pintype "passive"))
      (node (ref "R8") (pin "1") (pinfunction "1_1") (pintype "passive"))
      (node (ref "S3") (pin "3") (pinfunction "3_3") (pintype "passive"))
      (node (ref "S3") (pin "4") (pinfunction "4_4") (pintype "passive"))
      (node (ref "T1") (pin "E") (pinfunction "E_E") (pintype "passive"))
      (node (ref "U$1") (pin "2") (pinfunction "GND_2") (pintype "bidirectional"))
      (node (ref "U$3") (pin "3") (pinfunction "GND_3") (pintype "bidirectional"))
      (node (ref "U2") (pin "15") (pinfunction "GND_15") (pintype "power_in"))
      (node (ref "U2") (pin "23") (pinfunction "GND1_23") (pintype "power_in"))
      (node (ref "U2") (pin "33") (pinfunction "(#HWB)PE2_33") (pintype "bidirectional"))
      (node (ref "U2") (pin "35") (pinfunction "GND2_35") (pintype "power_in"))
      (node (ref "U2") (pin "43") (pinfunction "GND3_43") (pintype "power_in"))
      (node (ref "U2") (pin "5") (pinfunction "UGND_5") (pintype "power_in"))
      (node (ref "X1") (pin "1") (pinfunction "S_1") (pintype "passive"))
      (node (ref "Y2") (pin "2") (pinfunction "2_2") (pintype "passive"))
      (node (ref "Z1") (pin "2") (pinfunction "2_2") (pintype "passive"))
      (node (ref "Z2") (pin "2") (pinfunction "2_2") (pintype "passive"))
    )
    (net (code "44") (name "Net-(D2-PadA)") (class "Default")
      (node (ref "D2") (pin "A") (pinfunction "A_A") (pintype "passive"))
      (node (ref "ICSP") (pin "2") (pinfunction "2_2") (pintype "passive"))
    )
    (net (code "45") (name "Net-(IC4-C)") (class "Default")
      (node (ref "IC4") (pin "6") (pinfunction "C_6") (pintype "passive"))
      (node (ref "IC4") (pin "8") (pinfunction "C1_8") (pintype "passive"))
      (node (ref "R16") (pin "2") (pinfunction "2_2") (pintype "passive"))
      (node (ref "R17") (pin "2") (pinfunction "2_2") (pintype "passive"))
    )
    (net (code "46") (name "Net-(IC5-CC)") (class "Default")
      (node (ref "IC5") (pin "7") (pinfunction "CC_7") (pintype "output"))
      (node (ref "Q3") (pin "1") (pinfunction "G_1") (pintype "passive"))
      (node (ref "R19") (pin "1") (pinfunction "1_1") (pintype "passive"))
    )
    (net (code "47") (name "Net-(IC5-SNS)") (class "Default")
      (node (ref "IC5") (pin "1") (pinfunction "SNS_1") (pintype "input"))
      (node (ref "Q3") (pin "3") (pinfunction "S_3") (pintype "passive"))
      (node (ref "R25") (pin "1") (pinfunction "1_1") (pintype "passive"))
    )
    (net (code "48") (name "Net-(IC5-STAT)") (class "Default")
      (node (ref "IC5") (pin "5") (pinfunction "STAT_5") (pintype "output"))
      (node (ref "LED4") (pin "C") (pinfunction "C_C") (pintype "passive"))
      (node (ref "LED5") (pin "A") (pinfunction "A_A") (pintype "passive"))
    )
    (net (code "49") (name "Net-(IC5-TS)") (class "Default")
      (node (ref "IC5") (pin "4") (pinfunction "TS_4") (pintype "input"))
      (node (ref "R22") (pin "1") (pinfunction "1_1") (pintype "passive"))
      (node (ref "R23") (pin "1") (pinfunction "1_1") (pintype "passive"))
      (node (ref "R24") (pin "1") (pinfunction "1_1") (pintype "passive"))
    )
    (net (code "50") (name "Net-(ICSP-Pad5)") (class "Default")
      (node (ref "ICSP") (pin "5") (pinfunction "5_5") (pintype "passive"))
      (node (ref "S3") (pin "1") (pinfunction "1_1") (pintype "passive"))
      (node (ref "S3") (pin "2") (pinfunction "2_2") (pintype "passive"))
    )
    (net (code "51") (name "Net-(L-PadA)") (class "Default")
      (node (ref "L") (pin "A") (pinfunction "A_A") (pintype "passive"))
      (node (ref "R9") (pin "1") (pinfunction "1_1") (pintype "passive"))
    )
    (net (code "52") (name "Net-(LED4-PadA)") (class "Default")
      (node (ref "LED4") (pin "A") (pinfunction "A_A") (pintype "passive"))
      (node (ref "R20") (pin "1") (pinfunction "1_1") (pintype "passive"))
    )
    (net (code "53") (name "Net-(LED5-PadC)") (class "Default")
      (node (ref "LED5") (pin "C") (pinfunction "C_C") (pintype "passive"))
      (node (ref "R21") (pin "1") (pinfunction "1_1") (pintype "passive"))
    )
    (net (code "54") (name "Net-(ON-PadA)") (class "Default")
      (node (ref "ON") (pin "A") (pinfunction "A_A") (pintype "passive"))
      (node (ref "R12") (pin "1") (pinfunction "1_1") (pintype "passive"))
    )
    (net (code "55") (name "Net-(R2-Pad2)") (class "Default")
      (node (ref "R2") (pin "2") (pinfunction "2_2") (pintype "passive"))
      (node (ref "T1") (pin "B") (pinfunction "B_B") (pintype "passive"))
    )
    (net (code "56") (name "Net-(R10-Pad1)") (class "Default")
      (node (ref "R10") (pin "1") (pinfunction "1_1") (pintype "passive"))
      (node (ref "TX") (pin "A") (pinfunction "A_A") (pintype "passive"))
    )
    (net (code "57") (name "Net-(R11-Pad1)") (class "Default")
      (node (ref "R11") (pin "1") (pinfunction "1_1") (pintype "passive"))
      (node (ref "RX") (pin "A") (pinfunction "A_A") (pintype "passive"))
    )
    (net (code "58") (name "Net-(R15-Pad1)") (class "Default")
      (node (ref "R15") (pin "1") (pinfunction "1_1") (pintype "passive"))
      (node (ref "R3") (pin "2") (pinfunction "2_2") (pintype "passive"))
    )
    (net (code "59") (name "Net-(R18-Pad1)") (class "Default")
      (node (ref "R18") (pin "1") (pinfunction "1_1") (pintype "passive"))
      (node (ref "R25") (pin "2") (pinfunction "2_2") (pintype "passive"))
    )
    (net (code "60") (name "Net-(U$1-FB)") (class "Default")
      (node (ref "C15") (pin "1") (pinfunction "1_1") (pintype "passive"))
      (node (ref "R14") (pin "2") (pinfunction "2_2") (pintype "passive"))
      (node (ref "R15") (pin "2") (pinfunction "2_2") (pintype "passive"))
      (node (ref "U$1") (pin "3") (pinfunction "FB_3") (pintype "bidirectional"))
    )
    (net (code "61") (name "Net-(U$1-SW)") (class "Default")
      (node (ref "D3") (pin "A") (pinfunction "A_A") (pintype "passive"))
      (node (ref "U$1") (pin "1") (pinfunction "SW_1") (pintype "bidirectional"))
      (node (ref "U$2") (pin "P$2") (pinfunction "2_P$2") (pintype "passive"))
    )
    (net (code "62") (name "Net-(U$3-CAP+)") (class "Default")
      (node (ref "C18") (pin "+") (pinfunction "+_+") (pintype "passive"))
      (node (ref "C20") (pin "1") (pinfunction "1_1") (pintype "passive"))
      (node (ref "U$3") (pin "2") (pinfunction "CAP+_2") (pintype "bidirectional"))
    )
    (net (code "63") (name "Net-(U$3-CAP-)") (class "Default")
      (node (ref "C18") (pin "-") (pinfunction "-_-") (pintype "passive"))
      (node (ref "C20") (pin "2") (pinfunction "2_2") (pintype "passive"))
      (node (ref "U$3") (pin "4") (pinfunction "CAP-_4") (pintype "bidirectional"))
    )
    (net (code "64") (name "Net-(U$3-FC)") (class "Default")
      (node (ref "SJ1") (pin "1") (pinfunction "1_1") (pintype "passive"))
      (node (ref "U$3") (pin "1") (pinfunction "FC_1") (pintype "bidirectional"))
    )
    (net (code "65") (name "Net-(U2-(ADC0)PF0)") (class "Default")
      (node (ref "R7") (pin "2") (pinfunction "2_2") (pintype "passive"))
      (node (ref "U2") (pin "41") (pinfunction "(ADC0)PF0_41") (pintype "bidirectional"))
    )
    (net (code "66") (name "Net-(U2-AVCC)") (class "Default")
      (node (ref "C5") (pin "1") (pinfunction "1_1") (pintype "passive"))
      (node (ref "L1") (pin "2") (pinfunction "2_2") (pintype "passive"))
      (node (ref "U2") (pin "24") (pinfunction "AVCC_24") (pintype "power_in"))
      (node (ref "U2") (pin "44") (pinfunction "AVCC1_44") (pintype "power_in"))
    )
    (net (code "67") (name "Net-(U2-XTAL1)") (class "Default")
      (node (ref "C4") (pin "1") (pinfunction "1_1") (pintype "passive"))
      (node (ref "Q1") (pin "1") (pinfunction "1_1") (pintype "passive"))
      (node (ref "R1") (pin "1") (pinfunction "1_1") (pintype "passive"))
      (node (ref "U2") (pin "17") (pinfunction "XTAL1_17") (pintype "bidirectional"))
      (node (ref "Y2") (pin "3") (pinfunction "3_3") (pintype "passive"))
    )
    (net (code "68") (name "Net-(U2-XTAL2)") (class "Default")
      (node (ref "C3") (pin "1") (pinfunction "1_1") (pintype "passive"))
      (node (ref "Q1") (pin "2") (pinfunction "2_2") (pintype "passive"))
      (node (ref "R1") (pin "2") (pinfunction "2_2") (pintype "passive"))
      (node (ref "U2") (pin "16") (pinfunction "XTAL2_16") (pintype "bidirectional"))
      (node (ref "Y2") (pin "1") (pinfunction "1_1") (pintype "passive"))
    )
    (net (code "69") (name "VUSB") (class "Default")
      (node (ref "C8") (pin "1") (pinfunction "1_1") (pintype "passive"))
      (node (ref "C9") (pin "1") (pinfunction "1_1") (pintype "passive"))
      (node (ref "D1") (pin "A") (pinfunction "A_A") (pintype "passive"))
      (node (ref "D4") (pin "A") (pinfunction "A_A") (pintype "passive"))
      (node (ref "F1") (pin "1") (pinfunction "1_1") (pintype "passive"))
      (node (ref "R2") (pin "1") (pinfunction "1_1") (pintype "passive"))
      (node (ref "R8") (pin "2") (pinfunction "2_2") (pintype "passive"))
      (node (ref "U2") (pin "7") (pinfunction "VBUS_7") (pintype "input"))
    )
    (net (code "70") (name "unconnected-(IC4-NC-Pad1)") (class "Default")
      (node (ref "IC4") (pin "1") (pinfunction "NC_1") (pintype "no_connect"))
    )
    (net (code "71") (name "unconnected-(IC4-NC-Pad2)") (class "Default")
      (node (ref "IC4") (pin "2") (pinfunction "NC_2") (pintype "no_connect"))
    )
    (net (code "72") (name "unconnected-(IC4-NC-Pad3)") (class "Default")
      (node (ref "IC4") (pin "3") (pinfunction "NC_3") (pintype "no_connect"))
    )
    (net (code "73") (name "unconnected-(IC4-NC-Pad5)") (class "Default")
      (node (ref "IC4") (pin "5") (pinfunction "NC_5") (pintype "no_connect"))
    )
    (net (code "74") (name "unconnected-(IC4-NC-Pad7)") (class "Default")
      (node (ref "IC4") (pin "7") (pinfunction "NC_7") (pintype "no_connect"))
    )
    (net (code "75") (name "unconnected-(U$3-LV-Pad6)") (class "Default")
      (node (ref "U$3") (pin "6") (pinfunction "LV_6") (pintype "bidirectional"))
    )
    (net (code "76") (name "unconnected-(U$3-OSC-Pad7)") (class "Default")
      (node (ref "U$3") (pin "7") (pinfunction "OSC_7") (pintype "bidirectional"))
    )
  )
)
